# avr_programming_shield_rev_1.net
KiCad netlist of a schematic drawn in EAGLE
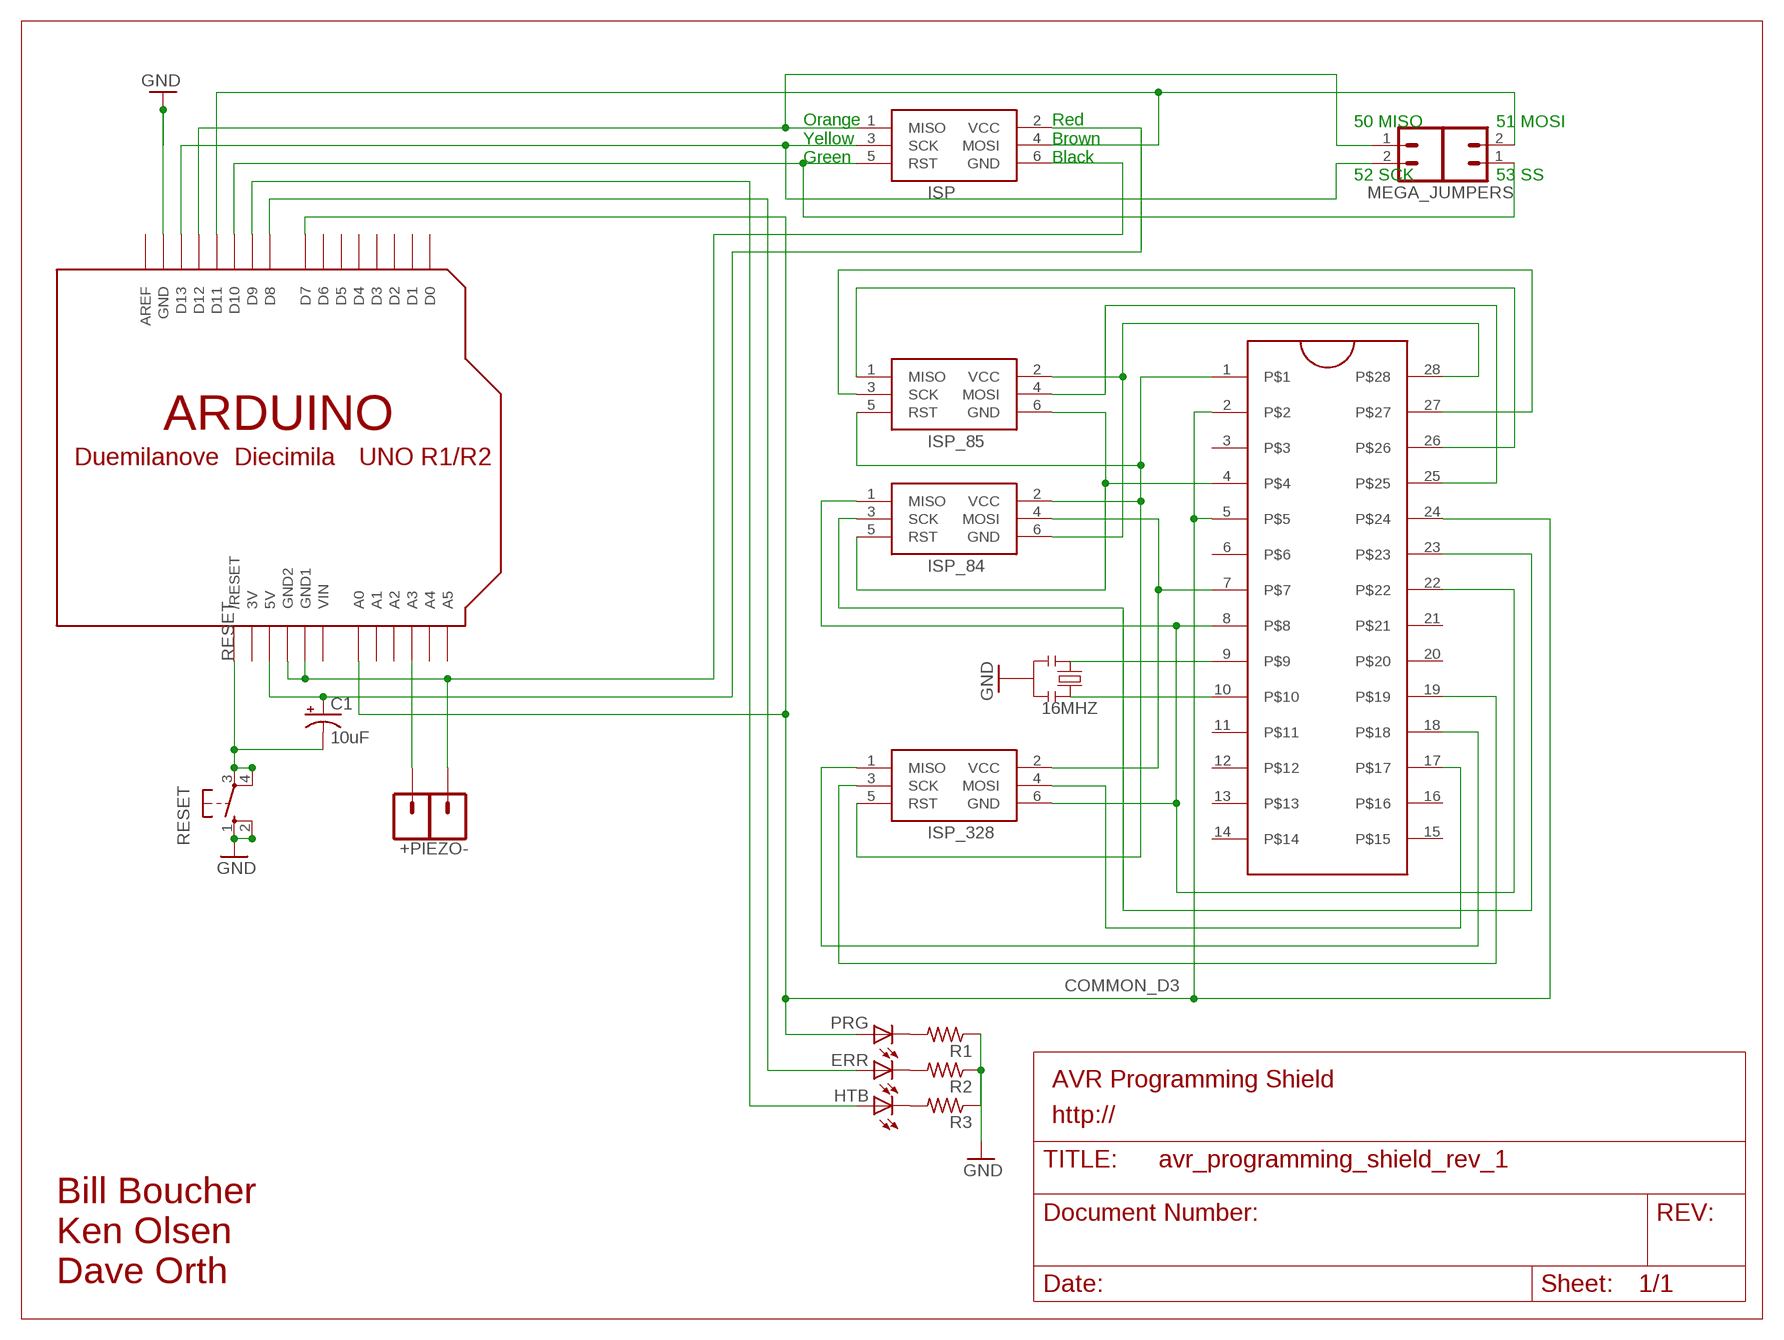
[diagram p0: schematic, sheet 1]

(export (version "E")
  (design (tool "Eeschema 10.0.6"))
  (components
    (comp (ref "+PIEZO-")
      (value "M01PTH")
      (footprint "eagle-import:1X01")
      (libsource (lib "eagle-import") (part "M01PTH"))
    )
    (comp (ref "16MHZ")
      (value "RESONATORPTH")
      (footprint "eagle-import:RESONATOR-PTH")
      (libsource (lib "eagle-import") (part "RESONATORPTH"))
    )
    (comp (ref "C1")
      (value "10uF")
      (footprint "eagle-import:CPOL-RADIAL-10UF-25V")
      (fields (field (name "MF") "ILLINOIS CAPACITOR,INC.") (field (name "MPN") "106TTA035M"))
      (libsource (lib "eagle-import") (part "CAP_POLPTH2"))
    )
    (comp (ref "ERR")
      (value "LED3MM")
      (footprint "eagle-import:LED3MM")
      (libsource (lib "eagle-import") (part "LED3MM"))
    )
    (comp (ref "HTB")
      (value "LED3MM")
      (footprint "eagle-import:LED3MM")
      (libsource (lib "eagle-import") (part "LED3MM"))
    )
    (comp (ref "ISP")
      (value "AVRISP-6")
      (footprint "eagle-import:AVRISP")
      (libsource (lib "eagle-import") (part "AVRISP-6"))
    )
    (comp (ref "ISP_84")
      (value "AVRISP-6")
      (footprint "eagle-import:AVRISP")
      (libsource (lib "eagle-import") (part "AVRISP-6"))
    )
    (comp (ref "ISP_85")
      (value "AVRISP-6")
      (footprint "eagle-import:AVRISP")
      (libsource (lib "eagle-import") (part "AVRISP-6"))
    )
    (comp (ref "ISP_328")
      (value "AVRISP-6")
      (footprint "eagle-import:AVRISP")
      (libsource (lib "eagle-import") (part "AVRISP-6"))
    )
    (comp (ref "JP2")
      (value "M02PTH")
      (footprint "eagle-import:1X02")
      (libsource (lib "eagle-import") (part "M02PTH"))
    )
    (comp (ref "JP4")
      (value "M01PTH")
      (footprint "eagle-import:1X01")
      (libsource (lib "eagle-import") (part "M01PTH"))
    )
    (comp (ref "MEGA_JUMPERS")
      (value "M02PTH")
      (footprint "eagle-import:1X02")
      (libsource (lib "eagle-import") (part "M02PTH"))
    )
    (comp (ref "PRG")
      (value "LED3MM")
      (footprint "eagle-import:LED3MM")
      (libsource (lib "eagle-import") (part "LED3MM"))
    )
    (comp (ref "R1")
      (value "R-US_0204/2V")
      (footprint "eagle-import:0204V")
      (libsource (lib "eagle-import") (part "R-US_0204/2V"))
    )
    (comp (ref "R2")
      (value "R-US_0204/2V")
      (footprint "eagle-import:0204V")
      (libsource (lib "eagle-import") (part "R-US_0204/2V"))
    )
    (comp (ref "R3")
      (value "R-US_0204/2V")
      (footprint "eagle-import:0204V")
      (libsource (lib "eagle-import") (part "R-US_0204/2V"))
    )
    (comp (ref "RESET")
      (value "10-XX")
      (footprint "eagle-import:B3F-10XX")
      (fields
        (field (name "MPN") "B3F-1000")
        (field (name "MPN_1") "B3F-1000")
        (field (name "OC_NEWARK") "36M3542")
      )
      (libsource (lib "eagle-import") (part "10-XX"))
    )
    (comp (ref "U$4")
      (value "ZIFSOCKET-28-3ZIFFSOCKET-28-3")
      (footprint "eagle-import:DIL28-3-ZIF_SOCKET")
      (libsource (lib "eagle-import") (part "ZIFSOCKET-28-3ZIFFSOCKET-28-3"))
    )
    (comp (ref "U$5")
      (value "ARDUINO-NOHOLE")
      (footprint "eagle-import:ARDUINO-NOHOLE")
      (libsource (lib "eagle-import") (part "ARDUINO-NOHOLE"))
    )
  )
  (nets
    (net (code "1") (name "/3V") (class "Default")
      (node (ref "U$5") (pin "3V") (pinfunction "3V_3V") (pintype "power_in"))
    )
    (net (code "2") (name "/COMMON_D3") (class "Default")
      (node (ref "PRG") (pin "A") (pinfunction "A_A") (pintype "passive"))
      (node (ref "U$4") (pin "2") (pinfunction "P$2_2") (pintype "bidirectional"))
      (node (ref "U$4") (pin "24") (pinfunction "P$24_24") (pintype "bidirectional"))
      (node (ref "U$4") (pin "5") (pinfunction "P$5_5") (pintype "bidirectional"))
      (node (ref "U$5") (pin "A0") (pinfunction "A0_A0") (pintype "bidirectional"))
      (node (ref "U$5") (pin "D7") (pinfunction "D7_D7") (pintype "bidirectional"))
    )
    (net (code "3") (name "/RESET") (class "Default")
      (node (ref "C1") (pin "2") (pinfunction "-_2") (pintype "passive"))
      (node (ref "RESET") (pin "3") (pinfunction "P_3") (pintype "passive"))
      (node (ref "RESET") (pin "4") (pinfunction "P1_4") (pintype "passive"))
      (node (ref "U$5") (pin "RESET") (pinfunction "/RESET_RESET") (pintype "bidirectional"))
    )
    (net (code "4") (name "/VIN") (class "Default")
      (node (ref "U$5") (pin "VIN") (pinfunction "VIN_VIN") (pintype "power_in"))
    )
    (net (code "5") (name "GND") (class "Default")
      (node (ref "+PIEZO-") (pin "1") (pinfunction "1_1") (pintype "passive"))
      (node (ref "16MHZ") (pin "2") (pinfunction "2_2") (pintype "passive"))
      (node (ref "ISP") (pin "6") (pinfunction "GND_6") (pintype "power_in"))
      (node (ref "R1") (pin "1") (pinfunction "1_1") (pintype "passive"))
      (node (ref "R2") (pin "1") (pinfunction "1_1") (pintype "passive"))
      (node (ref "R3") (pin "1") (pinfunction "1_1") (pintype "passive"))
      (node (ref "RESET") (pin "1") (pinfunction "S_1") (pintype "passive"))
      (node (ref "RESET") (pin "2") (pinfunction "S1_2") (pintype "passive"))
      (node (ref "U$5") (pin "GND") (pinfunction "GND_GND") (pintype "power_in"))
      (node (ref "U$5") (pin "GND1") (pinfunction "GND1_GND1") (pintype "power_in"))
      (node (ref "U$5") (pin "GND2") (pinfunction "GND2_GND2") (pintype "power_in"))
    )
    (net (code "6") (name "Net-(C1-+)") (class "Default")
      (node (ref "C1") (pin "1") (pinfunction "+_1") (pintype "passive"))
      (node (ref "ISP") (pin "2") (pinfunction "VCC_2") (pintype "power_in"))
      (node (ref "U$5") (pin "5V") (pinfunction "5V_5V") (pintype "power_in"))
    )
    (net (code "7") (name "Net-(ERR-C)") (class "Default")
      (node (ref "ERR") (pin "K") (pinfunction "C_K") (pintype "passive"))
      (node (ref "R2") (pin "2") (pinfunction "2_2") (pintype "passive"))
    )
    (net (code "8") (name "Net-(ERR-PadA)") (class "Default")
      (node (ref "ERR") (pin "A") (pinfunction "A_A") (pintype "passive"))
      (node (ref "U$5") (pin "D8") (pinfunction "D8_D8") (pintype "bidirectional"))
    )
    (net (code "9") (name "Net-(HTB-C)") (class "Default")
      (node (ref "HTB") (pin "K") (pinfunction "C_K") (pintype "passive"))
      (node (ref "R3") (pin "2") (pinfunction "2_2") (pintype "passive"))
    )
    (net (code "10") (name "Net-(HTB-PadA)") (class "Default")
      (node (ref "HTB") (pin "A") (pinfunction "A_A") (pintype "passive"))
      (node (ref "U$5") (pin "D9") (pinfunction "D9_D9") (pintype "bidirectional"))
    )
    (net (code "11") (name "Net-(ISP-MISO)") (class "Default")
      (node (ref "ISP") (pin "1") (pinfunction "MISO_1") (pintype "input"))
      (node (ref "MEGA_JUMPERS") (pin "1") (pinfunction "1_1") (pintype "passive"))
      (node (ref "U$5") (pin "D12") (pinfunction "D12_D12") (pintype "bidirectional"))
    )
    (net (code "12") (name "Net-(ISP-MOSI)") (class "Default")
      (node (ref "ISP") (pin "4") (pinfunction "MOSI_4") (pintype "output"))
      (node (ref "JP2") (pin "2") (pinfunction "2_2") (pintype "passive"))
      (node (ref "U$5") (pin "D11") (pinfunction "D11_D11") (pintype "bidirectional"))
    )
    (net (code "13") (name "Net-(ISP-RST)") (class "Default")
      (node (ref "ISP") (pin "5") (pinfunction "RST_5") (pintype "output"))
      (node (ref "JP2") (pin "1") (pinfunction "1_1") (pintype "passive"))
      (node (ref "U$5") (pin "D10") (pinfunction "D10_D10") (pintype "bidirectional"))
    )
    (net (code "14") (name "Net-(ISP-SCK)") (class "Default")
      (node (ref "ISP") (pin "3") (pinfunction "SCK_3") (pintype "output"))
      (node (ref "MEGA_JUMPERS") (pin "2") (pinfunction "2_2") (pintype "passive"))
      (node (ref "U$5") (pin "D13") (pinfunction "D13_D13") (pintype "bidirectional"))
    )
    (net (code "15") (name "Net-(ISP_84-GND)") (class "Default")
      (node (ref "ISP_84") (pin "6") (pinfunction "GND_6") (pintype "power_in"))
      (node (ref "ISP_85") (pin "2") (pinfunction "VCC_2") (pintype "power_in"))
      (node (ref "U$4") (pin "28") (pinfunction "P$28_28") (pintype "bidirectional"))
    )
    (net (code "16") (name "Net-(ISP_84-RST)") (class "Default")
      (node (ref "ISP_84") (pin "5") (pinfunction "RST_5") (pintype "output"))
      (node (ref "ISP_85") (pin "6") (pinfunction "GND_6") (pintype "power_in"))
      (node (ref "U$4") (pin "4") (pinfunction "P$4_4") (pintype "bidirectional"))
    )
    (net (code "17") (name "Net-(ISP_84-SCK)") (class "Default")
      (node (ref "ISP_84") (pin "3") (pinfunction "SCK_3") (pintype "output"))
      (node (ref "U$4") (pin "23") (pinfunction "P$23_23") (pintype "bidirectional"))
    )
    (net (code "18") (name "Net-(ISP_85-MISO)") (class "Default")
      (node (ref "ISP_85") (pin "1") (pinfunction "MISO_1") (pintype "input"))
      (node (ref "U$4") (pin "26") (pinfunction "P$26_26") (pintype "bidirectional"))
    )
    (net (code "19") (name "Net-(ISP_85-MOSI)") (class "Default")
      (node (ref "ISP_85") (pin "4") (pinfunction "MOSI_4") (pintype "output"))
      (node (ref "U$4") (pin "25") (pinfunction "P$25_25") (pintype "bidirectional"))
    )
    (net (code "20") (name "Net-(ISP_85-SCK)") (class "Default")
      (node (ref "ISP_85") (pin "3") (pinfunction "SCK_3") (pintype "output"))
      (node (ref "U$4") (pin "27") (pinfunction "P$27_27") (pintype "bidirectional"))
    )
    (net (code "21") (name "Net-(ISP_328-GND)") (class "Default")
      (node (ref "ISP_328") (pin "6") (pinfunction "GND_6") (pintype "power_in"))
      (node (ref "ISP_84") (pin "1") (pinfunction "MISO_1") (pintype "input"))
      (node (ref "U$4") (pin "22") (pinfunction "P$22_22") (pintype "bidirectional"))
      (node (ref "U$4") (pin "8") (pinfunction "P$8_8") (pintype "bidirectional"))
    )
    (net (code "22") (name "Net-(ISP_328-MISO)") (class "Default")
      (node (ref "ISP_328") (pin "1") (pinfunction "MISO_1") (pintype "input"))
      (node (ref "U$4") (pin "18") (pinfunction "P$18_18") (pintype "bidirectional"))
    )
    (net (code "23") (name "Net-(ISP_328-MOSI)") (class "Default")
      (node (ref "ISP_328") (pin "4") (pinfunction "MOSI_4") (pintype "output"))
      (node (ref "U$4") (pin "17") (pinfunction "P$17_17") (pintype "bidirectional"))
    )
    (net (code "24") (name "Net-(ISP_328-RST)") (class "Default")
      (node (ref "ISP_328") (pin "5") (pinfunction "RST_5") (pintype "output"))
      (node (ref "ISP_84") (pin "2") (pinfunction "VCC_2") (pintype "power_in"))
      (node (ref "ISP_85") (pin "5") (pinfunction "RST_5") (pintype "output"))
      (node (ref "U$4") (pin "1") (pinfunction "P$1_1") (pintype "bidirectional"))
    )
    (net (code "25") (name "Net-(ISP_328-SCK)") (class "Default")
      (node (ref "ISP_328") (pin "3") (pinfunction "SCK_3") (pintype "output"))
      (node (ref "U$4") (pin "19") (pinfunction "P$19_19") (pintype "bidirectional"))
    )
    (net (code "26") (name "Net-(ISP_328-VCC)") (class "Default")
      (node (ref "ISP_328") (pin "2") (pinfunction "VCC_2") (pintype "power_in"))
      (node (ref "ISP_84") (pin "4") (pinfunction "MOSI_4") (pintype "output"))
      (node (ref "U$4") (pin "7") (pinfunction "P$7_7") (pintype "bidirectional"))
    )
    (net (code "27") (name "Net-(JP4-Pad1)") (class "Default")
      (node (ref "JP4") (pin "1") (pinfunction "1_1") (pintype "passive"))
      (node (ref "U$5") (pin "A3") (pinfunction "A3_A3") (pintype "bidirectional"))
    )
    (net (code "28") (name "Net-(PRG-C)") (class "Default")
      (node (ref "PRG") (pin "K") (pinfunction "C_K") (pintype "passive"))
      (node (ref "R1") (pin "2") (pinfunction "2_2") (pintype "passive"))
    )
    (net (code "29") (name "Net-(U$4-P$9)") (class "Default")
      (node (ref "16MHZ") (pin "1") (pinfunction "1_1") (pintype "passive"))
      (node (ref "U$4") (pin "9") (pinfunction "P$9_9") (pintype "bidirectional"))
    )
    (net (code "30") (name "Net-(U$4-P$10)") (class "Default")
      (node (ref "16MHZ") (pin "3") (pinfunction "3_3") (pintype "passive"))
      (node (ref "U$4") (pin "10") (pinfunction "P$10_10") (pintype "bidirectional"))
    )
    (net (code "31") (name "unconnected-(U$4-P$3-Pad3)") (class "Default")
      (node (ref "U$4") (pin "3") (pinfunction "P$3_3") (pintype "bidirectional"))
    )
    (net (code "32") (name "unconnected-(U$4-P$6-Pad6)") (class "Default")
      (node (ref "U$4") (pin "6") (pinfunction "P$6_6") (pintype "bidirectional"))
    )
    (net (code "33") (name "unconnected-(U$4-P$11-Pad11)") (class "Default")
      (node (ref "U$4") (pin "11") (pinfunction "P$11_11") (pintype "bidirectional"))
    )
    (net (code "34") (name "unconnected-(U$4-P$12-Pad12)") (class "Default")
      (node (ref "U$4") (pin "12") (pinfunction "P$12_12") (pintype "bidirectional"))
    )
    (net (code "35") (name "unconnected-(U$4-P$13-Pad13)") (class "Default")
      (node (ref "U$4") (pin "13") (pinfunction "P$13_13") (pintype "bidirectional"))
    )
    (net (code "36") (name "unconnected-(U$4-P$14-Pad14)") (class "Default")
      (node (ref "U$4") (pin "14") (pinfunction "P$14_14") (pintype "bidirectional"))
    )
    (net (code "37") (name "unconnected-(U$4-P$15-Pad15)") (class "Default")
      (node (ref "U$4") (pin "15") (pinfunction "P$15_15") (pintype "bidirectional"))
    )
    (net (code "38") (name "unconnected-(U$4-P$16-Pad16)") (class "Default")
      (node (ref "U$4") (pin "16") (pinfunction "P$16_16") (pintype "bidirectional"))
    )
    (net (code "39") (name "unconnected-(U$4-P$20-Pad20)") (class "Default")
      (node (ref "U$4") (pin "20") (pinfunction "P$20_20") (pintype "bidirectional"))
    )
    (net (code "40") (name "unconnected-(U$4-P$21-Pad21)") (class "Default")
      (node (ref "U$4") (pin "21") (pinfunction "P$21_21") (pintype "bidirectional"))
    )
    (net (code "41") (name "unconnected-(U$5-PadA1)") (class "Default")
      (node (ref "U$5") (pin "A1") (pinfunction "A1_A1") (pintype "bidirectional"))
    )
    (net (code "42") (name "unconnected-(U$5-PadA2)") (class "Default")
      (node (ref "U$5") (pin "A2") (pinfunction "A2_A2") (pintype "bidirectional"))
    )
    (net (code "43") (name "unconnected-(U$5-PadA4)") (class "Default")
      (node (ref "U$5") (pin "A4") (pinfunction "A4_A4") (pintype "bidirectional"))
    )
    (net (code "44") (name "unconnected-(U$5-PadA5)") (class "Default")
      (node (ref "U$5") (pin "A5") (pinfunction "A5_A5") (pintype "bidirectional"))
    )
    (net (code "45") (name "unconnected-(U$5-PadAREF)") (class "Default")
      (node (ref "U$5") (pin "AREF") (pinfunction "AREF_AREF") (pintype "bidirectional"))
    )
    (net (code "46") (name "unconnected-(U$5-PadD0)") (class "Default")
      (node (ref "U$5") (pin "D0") (pinfunction "D0_D0") (pintype "bidirectional"))
    )
    (net (code "47") (name "unconnected-(U$5-PadD1)") (class "Default")
      (node (ref "U$5") (pin "D1") (pinfunction "D1_D1") (pintype "bidirectional"))
    )
    (net (code "48") (name "unconnected-(U$5-PadD2)") (class "Default")
      (node (ref "U$5") (pin "D2") (pinfunction "D2_D2") (pintype "bidirectional"))
    )
    (net (code "49") (name "unconnected-(U$5-PadD3)") (class "Default")
      (node (ref "U$5") (pin "D3") (pinfunction "D3_D3") (pintype "bidirectional"))
    )
    (net (code "50") (name "unconnected-(U$5-PadD4)") (class "Default")
      (node (ref "U$5") (pin "D4") (pinfunction "D4_D4") (pintype "bidirectional"))
    )
    (net (code "51") (name "unconnected-(U$5-PadD5)") (class "Default")
      (node (ref "U$5") (pin "D5") (pinfunction "D5_D5") (pintype "bidirectional"))
    )
    (net (code "52") (name "unconnected-(U$5-PadD6)") (class "Default")
      (node (ref "U$5") (pin "D6") (pinfunction "D6_D6") (pintype "bidirectional"))
    )
  )
)
